# Holoboard_peripherals.net
KiCad netlist of a schematic drawn in Altium Designer
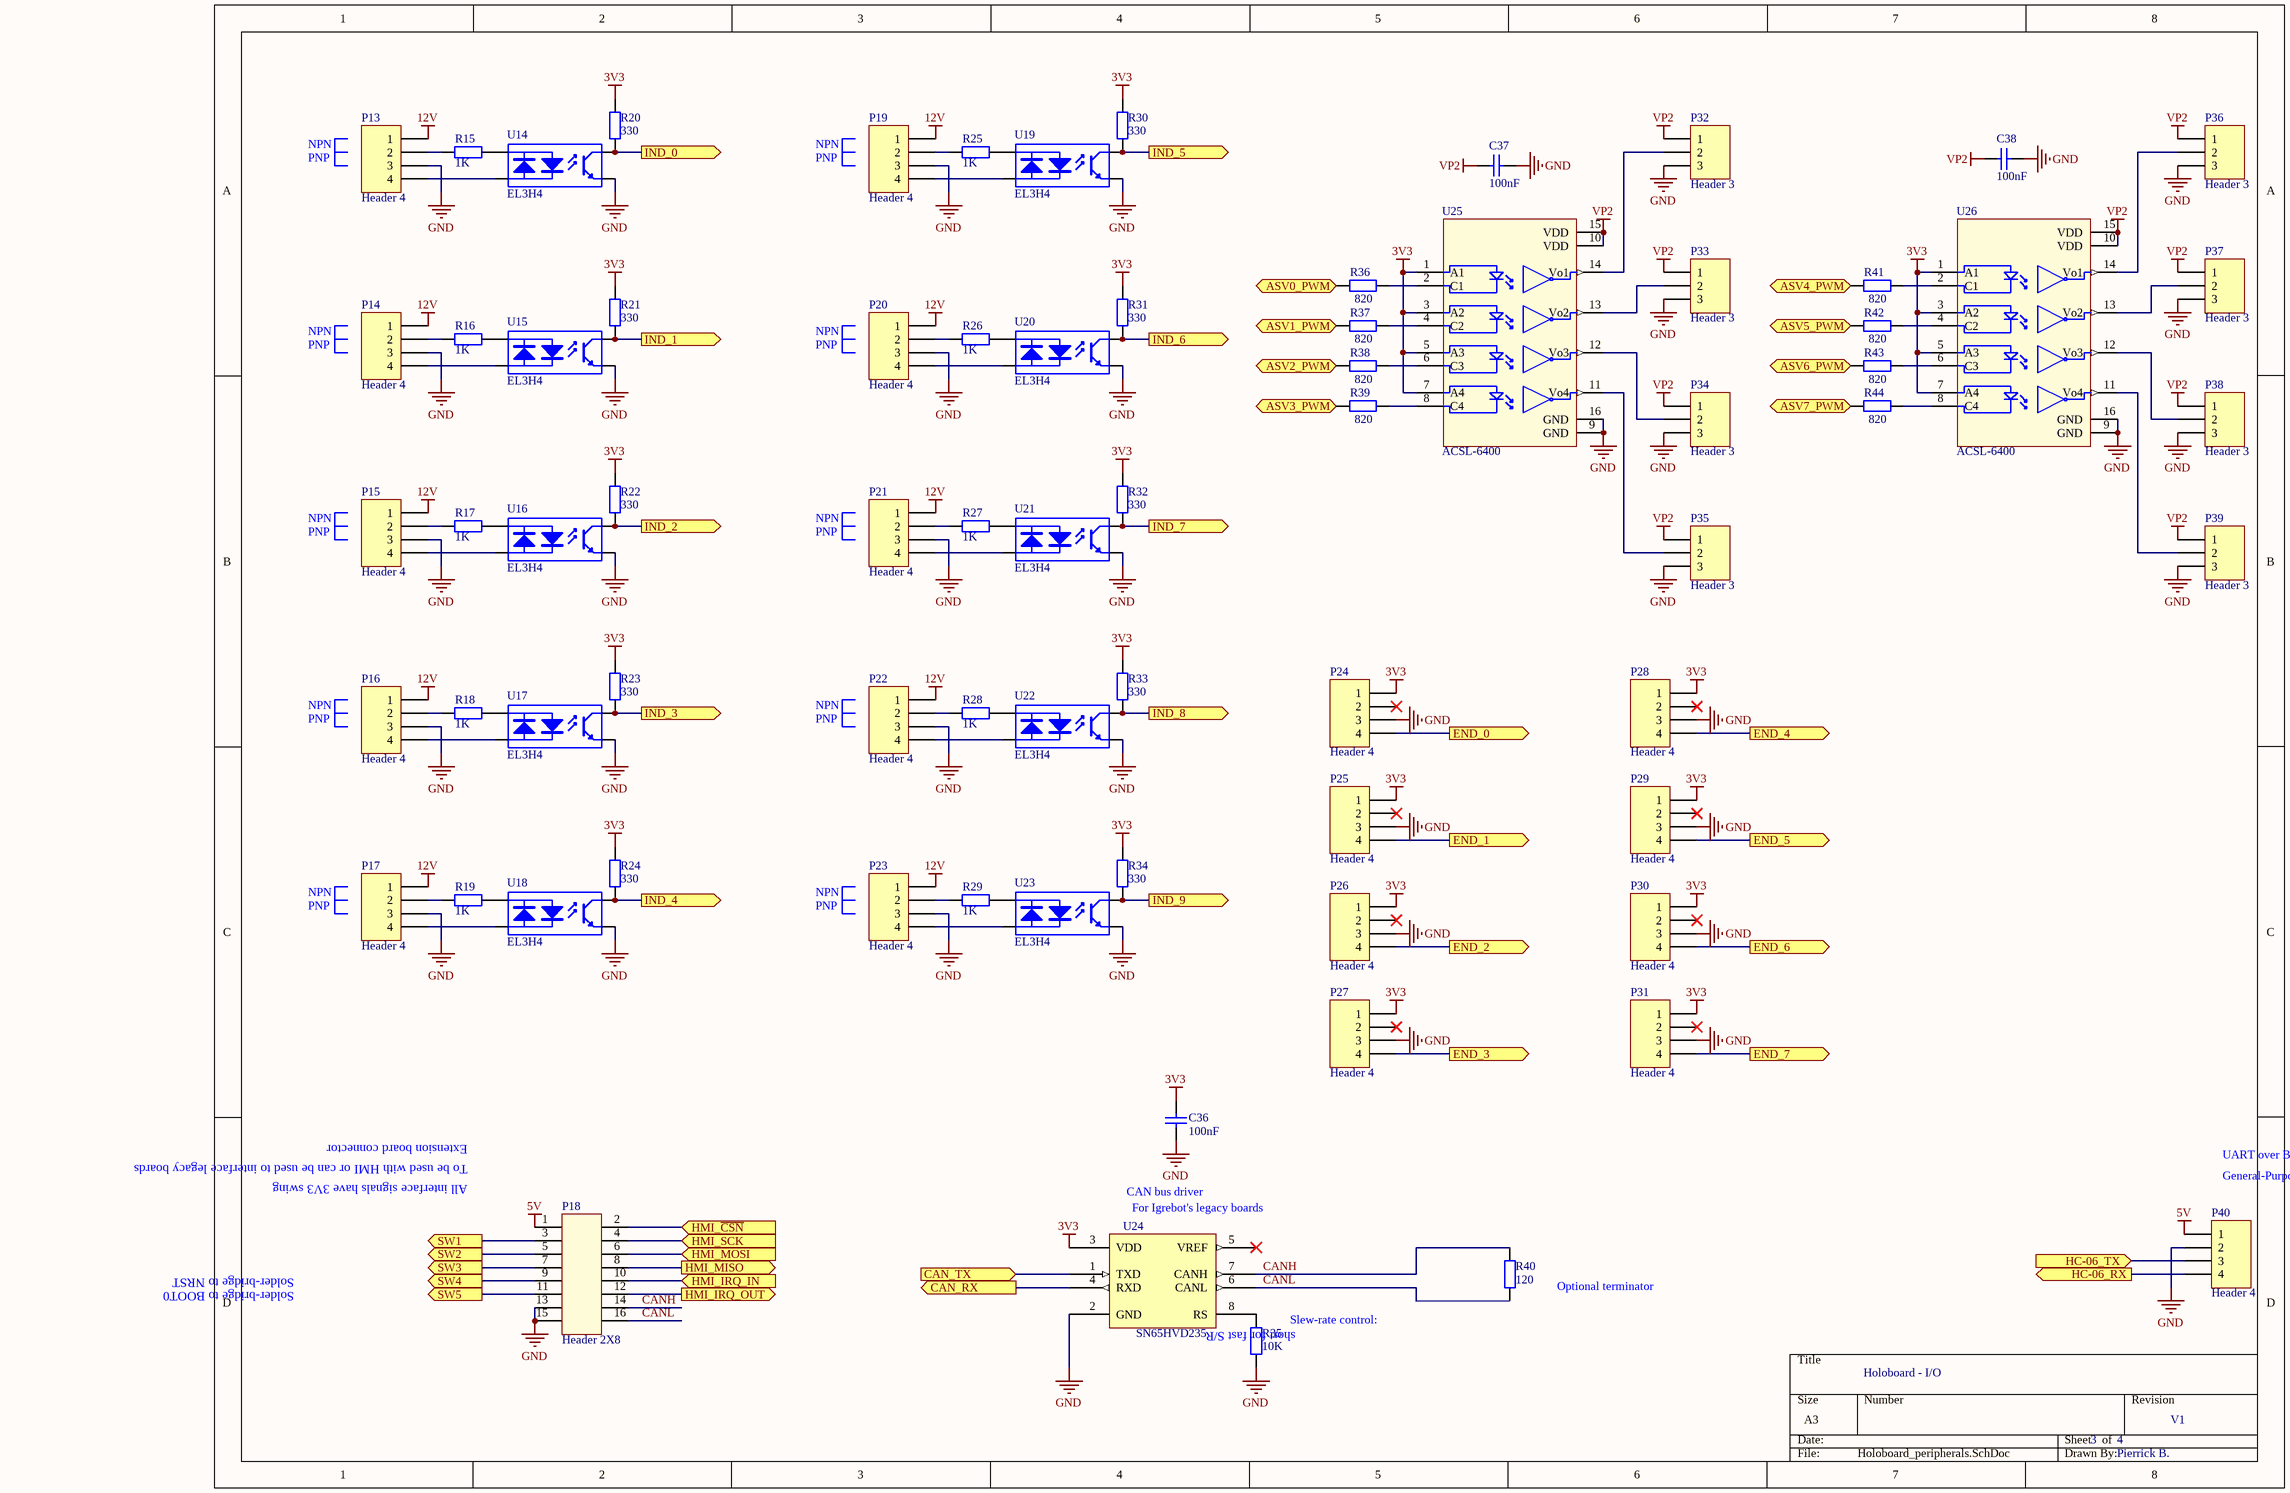
[diagram p0: Holoboard_peripherals.SchDoc]

(export (version "E")
  (design (tool "Eeschema 10.0.6"))
  (components
    (comp (ref "C36")
      (value "100nF")
      (footprint "C0603")
      (description "Capacitor")
      (fields (field (name "Comment") "Cap") (field (name "PUBLISHER") "Altium Limited"))
      (libsource (lib "Miscellaneous Devices") (part "Cap"))
    )
    (comp (ref "C37")
      (value "100nF")
      (footprint "C0603")
      (description "Capacitor")
      (fields (field (name "Comment") "Cap") (field (name "PUBLISHER") "Altium Limited"))
      (libsource (lib "Miscellaneous Devices") (part "Cap"))
    )
    (comp (ref "C38")
      (value "100nF")
      (footprint "C0603")
      (description "Capacitor")
      (fields (field (name "Comment") "Cap") (field (name "PUBLISHER") "Altium Limited"))
      (libsource (lib "Miscellaneous Devices") (part "Cap"))
    )
    (comp (ref "P13")
      (value "Header 4")
      (footprint "7-215079-4")
      (description "Header, 4-Pin")
      (fields (field (name "PUBLISHER") "Altium Limited"))
      (libsource (lib "LIBRARY IGREBOT") (part "Header 4"))
    )
    (comp (ref "P14")
      (value "Header 4")
      (footprint "7-215079-4")
      (description "Header, 4-Pin")
      (fields (field (name "PUBLISHER") "Altium Limited"))
      (libsource (lib "LIBRARY IGREBOT") (part "Header 4"))
    )
    (comp (ref "P15")
      (value "Header 4")
      (footprint "7-215079-4")
      (description "Header, 4-Pin")
      (fields (field (name "PUBLISHER") "Altium Limited"))
      (libsource (lib "LIBRARY IGREBOT") (part "Header 4"))
    )
    (comp (ref "P16")
      (value "Header 4")
      (footprint "7-215079-4")
      (description "Header, 4-Pin")
      (fields (field (name "PUBLISHER") "Altium Limited"))
      (libsource (lib "LIBRARY IGREBOT") (part "Header 4"))
    )
    (comp (ref "P17")
      (value "Header 4")
      (footprint "7-215079-4")
      (description "Header, 4-Pin")
      (fields (field (name "PUBLISHER") "Altium Limited"))
      (libsource (lib "LIBRARY IGREBOT") (part "Header 4"))
    )
    (comp (ref "P18")
      (value "Header 2X8")
      (footprint "HDR2X8")
      (libsource (lib "LIBRARY IGREBOT") (part "Header 2X8"))
    )
    (comp (ref "P19")
      (value "Header 4")
      (footprint "7-215079-4")
      (description "Header, 4-Pin")
      (fields (field (name "PUBLISHER") "Altium Limited"))
      (libsource (lib "LIBRARY IGREBOT") (part "Header 4"))
    )
    (comp (ref "P20")
      (value "Header 4")
      (footprint "7-215079-4")
      (description "Header, 4-Pin")
      (fields (field (name "PUBLISHER") "Altium Limited"))
      (libsource (lib "LIBRARY IGREBOT") (part "Header 4"))
    )
    (comp (ref "P21")
      (value "Header 4")
      (footprint "7-215079-4")
      (description "Header, 4-Pin")
      (fields (field (name "PUBLISHER") "Altium Limited"))
      (libsource (lib "LIBRARY IGREBOT") (part "Header 4"))
    )
    (comp (ref "P22")
      (value "Header 4")
      (footprint "7-215079-4")
      (description "Header, 4-Pin")
      (fields (field (name "PUBLISHER") "Altium Limited"))
      (libsource (lib "LIBRARY IGREBOT") (part "Header 4"))
    )
    (comp (ref "P23")
      (value "Header 4")
      (footprint "7-215079-4")
      (description "Header, 4-Pin")
      (fields (field (name "PUBLISHER") "Altium Limited"))
      (libsource (lib "LIBRARY IGREBOT") (part "Header 4"))
    )
    (comp (ref "P24")
      (value "Header 4")
      (footprint "7-215079-4")
      (description "Header, 4-Pin")
      (fields (field (name "PUBLISHER") "Altium Limited"))
      (libsource (lib "LIBRARY IGREBOT") (part "Header 4"))
    )
    (comp (ref "P25")
      (value "Header 4")
      (footprint "7-215079-4")
      (description "Header, 4-Pin")
      (fields (field (name "PUBLISHER") "Altium Limited"))
      (libsource (lib "LIBRARY IGREBOT") (part "Header 4"))
    )
    (comp (ref "P26")
      (value "Header 4")
      (footprint "7-215079-4")
      (description "Header, 4-Pin")
      (fields (field (name "PUBLISHER") "Altium Limited"))
      (libsource (lib "LIBRARY IGREBOT") (part "Header 4"))
    )
    (comp (ref "P27")
      (value "Header 4")
      (footprint "7-215079-4")
      (description "Header, 4-Pin")
      (fields (field (name "PUBLISHER") "Altium Limited"))
      (libsource (lib "LIBRARY IGREBOT") (part "Header 4"))
    )
    (comp (ref "P28")
      (value "Header 4")
      (footprint "7-215079-4")
      (description "Header, 4-Pin")
      (fields (field (name "PUBLISHER") "Altium Limited"))
      (libsource (lib "LIBRARY IGREBOT") (part "Header 4"))
    )
    (comp (ref "P29")
      (value "Header 4")
      (footprint "7-215079-4")
      (description "Header, 4-Pin")
      (fields (field (name "PUBLISHER") "Altium Limited"))
      (libsource (lib "LIBRARY IGREBOT") (part "Header 4"))
    )
    (comp (ref "P30")
      (value "Header 4")
      (footprint "7-215079-4")
      (description "Header, 4-Pin")
      (fields (field (name "PUBLISHER") "Altium Limited"))
      (libsource (lib "LIBRARY IGREBOT") (part "Header 4"))
    )
    (comp (ref "P31")
      (value "Header 4")
      (footprint "7-215079-4")
      (description "Header, 4-Pin")
      (fields (field (name "PUBLISHER") "Altium Limited"))
      (libsource (lib "LIBRARY IGREBOT") (part "Header 4"))
    )
    (comp (ref "P32")
      (value "Header 3")
      (footprint "HDR1X3")
      (description "Header, 3-Pin")
      (fields (field (name "PUBLISHER") "Altium Limited"))
      (libsource (lib "LIBRARY IGREBOT") (part "Header 3"))
    )
    (comp (ref "P33")
      (value "Header 3")
      (footprint "HDR1X3")
      (description "Header, 3-Pin")
      (fields (field (name "PUBLISHER") "Altium Limited"))
      (libsource (lib "LIBRARY IGREBOT") (part "Header 3"))
    )
    (comp (ref "P34")
      (value "Header 3")
      (footprint "HDR1X3")
      (description "Header, 3-Pin")
      (fields (field (name "PUBLISHER") "Altium Limited"))
      (libsource (lib "LIBRARY IGREBOT") (part "Header 3"))
    )
    (comp (ref "P35")
      (value "Header 3")
      (footprint "HDR1X3")
      (description "Header, 3-Pin")
      (fields (field (name "PUBLISHER") "Altium Limited"))
      (libsource (lib "LIBRARY IGREBOT") (part "Header 3"))
    )
    (comp (ref "P36")
      (value "Header 3")
      (footprint "HDR1X3")
      (description "Header, 3-Pin")
      (fields (field (name "PUBLISHER") "Altium Limited"))
      (libsource (lib "LIBRARY IGREBOT") (part "Header 3"))
    )
    (comp (ref "P37")
      (value "Header 3")
      (footprint "HDR1X3")
      (description "Header, 3-Pin")
      (fields (field (name "PUBLISHER") "Altium Limited"))
      (libsource (lib "LIBRARY IGREBOT") (part "Header 3"))
    )
    (comp (ref "P38")
      (value "Header 3")
      (footprint "HDR1X3")
      (description "Header, 3-Pin")
      (fields (field (name "PUBLISHER") "Altium Limited"))
      (libsource (lib "LIBRARY IGREBOT") (part "Header 3"))
    )
    (comp (ref "P39")
      (value "Header 3")
      (footprint "HDR1X3")
      (description "Header, 3-Pin")
      (fields (field (name "PUBLISHER") "Altium Limited"))
      (libsource (lib "LIBRARY IGREBOT") (part "Header 3"))
    )
    (comp (ref "P40")
      (value "Header 4")
      (footprint "HDR1X4")
      (description "Header, 4-Pin")
      (fields (field (name "PUBLISHER") "Altium Limited"))
      (libsource (lib "") (part "Header 4_1"))
    )
    (comp (ref "R15")
      (value "1K")
      (footprint "0603")
      (description "Resistor")
      (fields (field (name "Comment") "Res2") (field (name "PUBLISHER") "Altium Limited"))
      (libsource (lib "") (part "Res2_1"))
    )
    (comp (ref "R16")
      (value "1K")
      (footprint "0603")
      (description "Resistor")
      (fields (field (name "Comment") "Res2") (field (name "PUBLISHER") "Altium Limited"))
      (libsource (lib "") (part "Res2_1"))
    )
    (comp (ref "R17")
      (value "1K")
      (footprint "0603")
      (description "Resistor")
      (fields (field (name "Comment") "Res2") (field (name "PUBLISHER") "Altium Limited"))
      (libsource (lib "") (part "Res2_1"))
    )
    (comp (ref "R18")
      (value "1K")
      (footprint "0603")
      (description "Resistor")
      (fields (field (name "Comment") "Res2") (field (name "PUBLISHER") "Altium Limited"))
      (libsource (lib "") (part "Res2_1"))
    )
    (comp (ref "R19")
      (value "1K")
      (footprint "0603")
      (description "Resistor")
      (fields (field (name "Comment") "Res2") (field (name "PUBLISHER") "Altium Limited"))
      (libsource (lib "") (part "Res2_1"))
    )
    (comp (ref "R20")
      (value "330")
      (footprint "0603")
      (description "Resistor")
      (fields (field (name "Comment") "Res2") (field (name "PUBLISHER") "Altium Limited"))
      (libsource (lib "LIBRARY IGREBOT") (part "Res2"))
    )
    (comp (ref "R21")
      (value "330")
      (footprint "0603")
      (description "Resistor")
      (fields (field (name "Comment") "Res2") (field (name "PUBLISHER") "Altium Limited"))
      (libsource (lib "LIBRARY IGREBOT") (part "Res2"))
    )
    (comp (ref "R22")
      (value "330")
      (footprint "0603")
      (description "Resistor")
      (fields (field (name "Comment") "Res2") (field (name "PUBLISHER") "Altium Limited"))
      (libsource (lib "LIBRARY IGREBOT") (part "Res2"))
    )
    (comp (ref "R23")
      (value "330")
      (footprint "0603")
      (description "Resistor")
      (fields (field (name "Comment") "Res2") (field (name "PUBLISHER") "Altium Limited"))
      (libsource (lib "LIBRARY IGREBOT") (part "Res2"))
    )
    (comp (ref "R24")
      (value "330")
      (footprint "0603")
      (description "Resistor")
      (fields (field (name "Comment") "Res2") (field (name "PUBLISHER") "Altium Limited"))
      (libsource (lib "LIBRARY IGREBOT") (part "Res2"))
    )
    (comp (ref "R25")
      (value "1K")
      (footprint "0603")
      (description "Resistor")
      (fields (field (name "Comment") "Res2") (field (name "PUBLISHER") "Altium Limited"))
      (libsource (lib "") (part "Res2_1"))
    )
    (comp (ref "R26")
      (value "1K")
      (footprint "0603")
      (description "Resistor")
      (fields (field (name "Comment") "Res2") (field (name "PUBLISHER") "Altium Limited"))
      (libsource (lib "") (part "Res2_1"))
    )
    (comp (ref "R27")
      (value "1K")
      (footprint "0603")
      (description "Resistor")
      (fields (field (name "Comment") "Res2") (field (name "PUBLISHER") "Altium Limited"))
      (libsource (lib "") (part "Res2_1"))
    )
    (comp (ref "R28")
      (value "1K")
      (footprint "0603")
      (description "Resistor")
      (fields (field (name "Comment") "Res2") (field (name "PUBLISHER") "Altium Limited"))
      (libsource (lib "") (part "Res2_1"))
    )
    (comp (ref "R29")
      (value "1K")
      (footprint "0603")
      (description "Resistor")
      (fields (field (name "Comment") "Res2") (field (name "PUBLISHER") "Altium Limited"))
      (libsource (lib "") (part "Res2_1"))
    )
    (comp (ref "R30")
      (value "330")
      (footprint "0603")
      (description "Resistor")
      (fields (field (name "Comment") "Res2") (field (name "PUBLISHER") "Altium Limited"))
      (libsource (lib "LIBRARY IGREBOT") (part "Res2"))
    )
    (comp (ref "R31")
      (value "330")
      (footprint "0603")
      (description "Resistor")
      (fields (field (name "Comment") "Res2") (field (name "PUBLISHER") "Altium Limited"))
      (libsource (lib "LIBRARY IGREBOT") (part "Res2"))
    )
    (comp (ref "R32")
      (value "330")
      (footprint "0603")
      (description "Resistor")
      (fields (field (name "Comment") "Res2") (field (name "PUBLISHER") "Altium Limited"))
      (libsource (lib "LIBRARY IGREBOT") (part "Res2"))
    )
    (comp (ref "R33")
      (value "330")
      (footprint "0603")
      (description "Resistor")
      (fields (field (name "Comment") "Res2") (field (name "PUBLISHER") "Altium Limited"))
      (libsource (lib "LIBRARY IGREBOT") (part "Res2"))
    )
    (comp (ref "R34")
      (value "330")
      (footprint "0603")
      (description "Resistor")
      (fields (field (name "Comment") "Res2") (field (name "PUBLISHER") "Altium Limited"))
      (libsource (lib "LIBRARY IGREBOT") (part "Res2"))
    )
    (comp (ref "R35")
      (value "10K")
      (footprint "0603")
      (description "Resistor")
      (fields (field (name "Comment") "Res2") (field (name "PUBLISHER") "Altium Limited"))
      (libsource (lib "*") (part "Res2"))
    )
    (comp (ref "R36")
      (value "820")
      (footprint "0603")
      (description "Resistor")
      (fields (field (name "Comment") "Res2") (field (name "PUBLISHER") "Altium Limited"))
      (libsource (lib "") (part "Res2_2"))
    )
    (comp (ref "R37")
      (value "820")
      (footprint "0603")
      (description "Resistor")
      (fields (field (name "Comment") "Res2") (field (name "PUBLISHER") "Altium Limited"))
      (libsource (lib "") (part "Res2_2"))
    )
    (comp (ref "R38")
      (value "820")
      (footprint "0603")
      (description "Resistor")
      (fields (field (name "Comment") "Res2") (field (name "PUBLISHER") "Altium Limited"))
      (libsource (lib "") (part "Res2_2"))
    )
    (comp (ref "R39")
      (value "820")
      (footprint "0603")
      (description "Resistor")
      (fields (field (name "Comment") "Res2") (field (name "PUBLISHER") "Altium Limited"))
      (libsource (lib "") (part "Res2_2"))
    )
    (comp (ref "R40")
      (value "120")
      (footprint "0603")
      (description "Resistor")
      (fields (field (name "Comment") "Res2") (field (name "PUBLISHER") "Altium Limited"))
      (libsource (lib "") (part "Res2_1"))
    )
    (comp (ref "R41")
      (value "820")
      (footprint "0603")
      (description "Resistor")
      (fields (field (name "Comment") "Res2") (field (name "PUBLISHER") "Altium Limited"))
      (libsource (lib "") (part "Res2_2"))
    )
    (comp (ref "R42")
      (value "820")
      (footprint "0603")
      (description "Resistor")
      (fields (field (name "Comment") "Res2") (field (name "PUBLISHER") "Altium Limited"))
      (libsource (lib "") (part "Res2_2"))
    )
    (comp (ref "R43")
      (value "820")
      (footprint "0603")
      (description "Resistor")
      (fields (field (name "Comment") "Res2") (field (name "PUBLISHER") "Altium Limited"))
      (libsource (lib "") (part "Res2_2"))
    )
    (comp (ref "R44")
      (value "820")
      (footprint "0603")
      (description "Resistor")
      (fields (field (name "Comment") "Res2") (field (name "PUBLISHER") "Altium Limited"))
      (libsource (lib "") (part "Res2_2"))
    )
    (comp (ref "U14")
      (value "EL3H4")
      (description "4-Pin Phototransistor, AC input")
      (fields (field (name "PUBLISHER") "Altium Limited"))
      (libsource (lib "LIBRARY IGREBOT") (part "EL3H4"))
    )
    (comp (ref "U15")
      (value "EL3H4")
      (description "4-Pin Phototransistor, AC input")
      (fields (field (name "PUBLISHER") "Altium Limited"))
      (libsource (lib "LIBRARY IGREBOT") (part "EL3H4"))
    )
    (comp (ref "U16")
      (value "EL3H4")
      (description "4-Pin Phototransistor, AC input")
      (fields (field (name "PUBLISHER") "Altium Limited"))
      (libsource (lib "LIBRARY IGREBOT") (part "EL3H4"))
    )
    (comp (ref "U17")
      (value "EL3H4")
      (description "4-Pin Phototransistor, AC input")
      (fields (field (name "PUBLISHER") "Altium Limited"))
      (libsource (lib "LIBRARY IGREBOT") (part "EL3H4"))
    )
    (comp (ref "U18")
      (value "EL3H4")
      (description "4-Pin Phototransistor, AC input")
      (fields (field (name "PUBLISHER") "Altium Limited"))
      (libsource (lib "LIBRARY IGREBOT") (part "EL3H4"))
    )
    (comp (ref "U19")
      (value "EL3H4")
      (description "4-Pin Phototransistor, AC input")
      (fields (field (name "PUBLISHER") "Altium Limited"))
      (libsource (lib "LIBRARY IGREBOT") (part "EL3H4"))
    )
    (comp (ref "U20")
      (value "EL3H4")
      (description "4-Pin Phototransistor, AC input")
      (fields (field (name "PUBLISHER") "Altium Limited"))
      (libsource (lib "LIBRARY IGREBOT") (part "EL3H4"))
    )
    (comp (ref "U21")
      (value "EL3H4")
      (description "4-Pin Phototransistor, AC input")
      (fields (field (name "PUBLISHER") "Altium Limited"))
      (libsource (lib "LIBRARY IGREBOT") (part "EL3H4"))
    )
    (comp (ref "U22")
      (value "EL3H4")
      (description "4-Pin Phototransistor, AC input")
      (fields (field (name "PUBLISHER") "Altium Limited"))
      (libsource (lib "LIBRARY IGREBOT") (part "EL3H4"))
    )
    (comp (ref "U23")
      (value "EL3H4")
      (description "4-Pin Phototransistor, AC input")
      (fields (field (name "PUBLISHER") "Altium Limited"))
      (libsource (lib "LIBRARY IGREBOT") (part "EL3H4"))
    )
    (comp (ref "U24")
      (value "SN65HVD235")
      (footprint "SOIC150-8")
      (description "High Speed Can Transceiver")
      (fields (field (name "PUBLISHER") "Altium Limited"))
      (libsource (lib "*") (part "MCP2551"))
    )
    (comp (ref "U25")
      (value "ACSL-6400")
      (footprint "SO16")
      (libsource (lib "LIBRARY IGREBOT") (part "ACSL-6400"))
    )
    (comp (ref "U26")
      (value "ACSL-6400")
      (footprint "SO16")
      (libsource (lib "LIBRARY IGREBOT") (part "ACSL-6400"))
    )
  )
  (nets
    (net (code "1") (name "/ASV0_PWM") (class "Default")
      (node (ref "R36") (pin "1") (pinfunction "1_1") (pintype "passive"))
    )
    (net (code "2") (name "/ASV1_PWM") (class "Default")
      (node (ref "R37") (pin "1") (pinfunction "1_1") (pintype "passive"))
    )
    (net (code "3") (name "/ASV2_PWM") (class "Default")
      (node (ref "R38") (pin "1") (pinfunction "1_1") (pintype "passive"))
    )
    (net (code "4") (name "/ASV3_PWM") (class "Default")
      (node (ref "R39") (pin "1") (pinfunction "1_1") (pintype "passive"))
    )
    (net (code "5") (name "/ASV4_PWM") (class "Default")
      (node (ref "R41") (pin "1") (pinfunction "1_1") (pintype "passive"))
    )
    (net (code "6") (name "/ASV5_PWM") (class "Default")
      (node (ref "R42") (pin "1") (pinfunction "1_1") (pintype "passive"))
    )
    (net (code "7") (name "/ASV6_PWM") (class "Default")
      (node (ref "R43") (pin "1") (pinfunction "1_1") (pintype "passive"))
    )
    (net (code "8") (name "/ASV7_PWM") (class "Default")
      (node (ref "R44") (pin "1") (pinfunction "1_1") (pintype "passive"))
    )
    (net (code "9") (name "/CANH") (class "Default")
      (node (ref "P18") (pin "14") (pinfunction "14_14") (pintype "passive"))
      (node (ref "R40") (pin "1") (pinfunction "1_1") (pintype "passive"))
      (node (ref "U24") (pin "7") (pinfunction "CANH_7") (pintype "output"))
    )
    (net (code "10") (name "/CANL") (class "Default")
      (node (ref "P18") (pin "16") (pinfunction "16_16") (pintype "passive"))
      (node (ref "R40") (pin "2") (pinfunction "2_2") (pintype "passive"))
      (node (ref "U24") (pin "6") (pinfunction "CANL_6") (pintype "output"))
    )
    (net (code "11") (name "/CAN_RX") (class "Default")
      (node (ref "U24") (pin "4") (pinfunction "RXD_4") (pintype "output"))
    )
    (net (code "12") (name "/CAN_TX") (class "Default")
      (node (ref "U24") (pin "1") (pinfunction "TXD_1") (pintype "input"))
    )
    (net (code "13") (name "/END_0") (class "Default")
      (node (ref "P24") (pin "4") (pinfunction "4_4") (pintype "passive"))
    )
    (net (code "14") (name "/END_1") (class "Default")
      (node (ref "P25") (pin "4") (pinfunction "4_4") (pintype "passive"))
    )
    (net (code "15") (name "/END_2") (class "Default")
      (node (ref "P26") (pin "4") (pinfunction "4_4") (pintype "passive"))
    )
    (net (code "16") (name "/END_3") (class "Default")
      (node (ref "P27") (pin "4") (pinfunction "4_4") (pintype "passive"))
    )
    (net (code "17") (name "/END_4") (class "Default")
      (node (ref "P28") (pin "4") (pinfunction "4_4") (pintype "passive"))
    )
    (net (code "18") (name "/END_5") (class "Default")
      (node (ref "P29") (pin "4") (pinfunction "4_4") (pintype "passive"))
    )
    (net (code "19") (name "/END_6") (class "Default")
      (node (ref "P30") (pin "4") (pinfunction "4_4") (pintype "passive"))
    )
    (net (code "20") (name "/END_7") (class "Default")
      (node (ref "P31") (pin "4") (pinfunction "4_4") (pintype "passive"))
    )
    (net (code "21") (name "/HC-06_RX") (class "Default")
      (node (ref "P40") (pin "4") (pinfunction "4_4") (pintype "passive"))
    )
    (net (code "22") (name "/HC-06_TX") (class "Default")
      (node (ref "P40") (pin "3") (pinfunction "3_3") (pintype "passive"))
    )
    (net (code "23") (name "/HMI_IRQ_IN") (class "Default")
      (node (ref "P18") (pin "10") (pinfunction "10_10") (pintype "passive"))
    )
    (net (code "24") (name "/HMI_IRQ_OUT") (class "Default")
      (node (ref "P18") (pin "12") (pinfunction "12_12") (pintype "passive"))
    )
    (net (code "25") (name "/HMI_MISO") (class "Default")
      (node (ref "P18") (pin "8") (pinfunction "8_8") (pintype "passive"))
    )
    (net (code "26") (name "/HMI_MOSI") (class "Default")
      (node (ref "P18") (pin "6") (pinfunction "6_6") (pintype "passive"))
    )
    (net (code "27") (name "/HMI_SCK") (class "Default")
      (node (ref "P18") (pin "4") (pinfunction "4_4") (pintype "passive"))
    )
    (net (code "28") (name "/HMI_~{CSN}") (class "Default")
      (node (ref "P18") (pin "2") (pinfunction "2_2") (pintype "passive"))
    )
    (net (code "29") (name "/IND_0") (class "Default")
      (node (ref "R20") (pin "2") (pinfunction "2_2") (pintype "passive"))
      (node (ref "U14") (pin "4") (pinfunction "C_4") (pintype "passive"))
    )
    (net (code "30") (name "/IND_1") (class "Default")
      (node (ref "R21") (pin "2") (pinfunction "2_2") (pintype "passive"))
      (node (ref "U15") (pin "4") (pinfunction "C_4") (pintype "passive"))
    )
    (net (code "31") (name "/IND_2") (class "Default")
      (node (ref "R22") (pin "2") (pinfunction "2_2") (pintype "passive"))
      (node (ref "U16") (pin "4") (pinfunction "C_4") (pintype "passive"))
    )
    (net (code "32") (name "/IND_3") (class "Default")
      (node (ref "R23") (pin "2") (pinfunction "2_2") (pintype "passive"))
      (node (ref "U17") (pin "4") (pinfunction "C_4") (pintype "passive"))
    )
    (net (code "33") (name "/IND_4") (class "Default")
      (node (ref "R24") (pin "2") (pinfunction "2_2") (pintype "passive"))
      (node (ref "U18") (pin "4") (pinfunction "C_4") (pintype "passive"))
    )
    (net (code "34") (name "/IND_5") (class "Default")
      (node (ref "R30") (pin "2") (pinfunction "2_2") (pintype "passive"))
      (node (ref "U19") (pin "4") (pinfunction "C_4") (pintype "passive"))
    )
    (net (code "35") (name "/IND_6") (class "Default")
      (node (ref "R31") (pin "2") (pinfunction "2_2") (pintype "passive"))
      (node (ref "U20") (pin "4") (pinfunction "C_4") (pintype "passive"))
    )
    (net (code "36") (name "/IND_7") (class "Default")
      (node (ref "R32") (pin "2") (pinfunction "2_2") (pintype "passive"))
      (node (ref "U21") (pin "4") (pinfunction "C_4") (pintype "passive"))
    )
    (net (code "37") (name "/IND_8") (class "Default")
      (node (ref "R33") (pin "2") (pinfunction "2_2") (pintype "passive"))
      (node (ref "U22") (pin "4") (pinfunction "C_4") (pintype "passive"))
    )
    (net (code "38") (name "/IND_9") (class "Default")
      (node (ref "R34") (pin "2") (pinfunction "2_2") (pintype "passive"))
      (node (ref "U23") (pin "4") (pinfunction "C_4") (pintype "passive"))
    )
    (net (code "39") (name "/SW1") (class "Default")
      (node (ref "P18") (pin "3") (pinfunction "3_3") (pintype "passive"))
    )
    (net (code "40") (name "/SW2") (class "Default")
      (node (ref "P18") (pin "5") (pinfunction "5_5") (pintype "passive"))
    )
    (net (code "41") (name "/SW3") (class "Default")
      (node (ref "P18") (pin "7") (pinfunction "7_7") (pintype "passive"))
    )
    (net (code "42") (name "/SW4") (class "Default")
      (node (ref "P18") (pin "9") (pinfunction "9_9") (pintype "passive"))
    )
    (net (code "43") (name "/SW5") (class "Default")
      (node (ref "P18") (pin "11") (pinfunction "11_11") (pintype "passive"))
    )
    (net (code "44") (name "3V3") (class "Default")
      (node (ref "C36") (pin "2") (pinfunction "2_2") (pintype "passive"))
      (node (ref "P24") (pin "1") (pinfunction "1_1") (pintype "passive"))
      (node (ref "P25") (pin "1") (pinfunction "1_1") (pintype "passive"))
      (node (ref "P26") (pin "1") (pinfunction "1_1") (pintype "passive"))
      (node (ref "P27") (pin "1") (pinfunction "1_1") (pintype "passive"))
      (node (ref "P28") (pin "1") (pinfunction "1_1") (pintype "passive"))
      (node (ref "P29") (pin "1") (pinfunction "1_1") (pintype "passive"))
      (node (ref "P30") (pin "1") (pinfunction "1_1") (pintype "passive"))
      (node (ref "P31") (pin "1") (pinfunction "1_1") (pintype "passive"))
      (node (ref "R20") (pin "1") (pinfunction "1_1") (pintype "passive"))
      (node (ref "R21") (pin "1") (pinfunction "1_1") (pintype "passive"))
      (node (ref "R22") (pin "1") (pinfunction "1_1") (pintype "passive"))
      (node (ref "R23") (pin "1") (pinfunction "1_1") (pintype "passive"))
      (node (ref "R24") (pin "1") (pinfunction "1_1") (pintype "passive"))
      (node (ref "R30") (pin "1") (pinfunction "1_1") (pintype "passive"))
      (node (ref "R31") (pin "1") (pinfunction "1_1") (pintype "passive"))
      (node (ref "R32") (pin "1") (pinfunction "1_1") (pintype "passive"))
      (node (ref "R33") (pin "1") (pinfunction "1_1") (pintype "passive"))
      (node (ref "R34") (pin "1") (pinfunction "1_1") (pintype "passive"))
      (node (ref "U24") (pin "3") (pinfunction "VDD_3") (pintype "power_in"))
      (node (ref "U25") (pin "1") (pinfunction "A1_1") (pintype "power_in"))
      (node (ref "U25") (pin "3") (pinfunction "A2_3") (pintype "passive"))
      (node (ref "U25") (pin "5") (pinfunction "A3_5") (pintype "passive"))
      (node (ref "U25") (pin "7") (pinfunction "A4_7") (pintype "passive"))
      (node (ref "U26") (pin "1") (pinfunction "A1_1") (pintype "power_in"))
      (node (ref "U26") (pin "3") (pinfunction "A2_3") (pintype "passive"))
      (node (ref "U26") (pin "5") (pinfunction "A3_5") (pintype "passive"))
      (node (ref "U26") (pin "7") (pinfunction "A4_7") (pintype "passive"))
    )
    (net (code "45") (name "5V") (class "Default")
      (node (ref "P18") (pin "1") (pinfunction "1_1") (pintype "passive"))
      (node (ref "P40") (pin "1") (pinfunction "1_1") (pintype "passive"))
    )
    (net (code "46") (name "12V") (class "Default")
      (node (ref "P13") (pin "1") (pinfunction "1_1") (pintype "passive"))
      (node (ref "P14") (pin "1") (pinfunction "1_1") (pintype "passive"))
      (node (ref "P15") (pin "1") (pinfunction "1_1") (pintype "passive"))
      (node (ref "P16") (pin "1") (pinfunction "1_1") (pintype "passive"))
      (node (ref "P17") (pin "1") (pinfunction "1_1") (pintype "passive"))
      (node (ref "P19") (pin "1") (pinfunction "1_1") (pintype "passive"))
      (node (ref "P20") (pin "1") (pinfunction "1_1") (pintype "passive"))
      (node (ref "P21") (pin "1") (pinfunction "1_1") (pintype "passive"))
      (node (ref "P22") (pin "1") (pinfunction "1_1") (pintype "passive"))
      (node (ref "P23") (pin "1") (pinfunction "1_1") (pintype "passive"))
    )
    (net (code "47") (name "GND") (class "Default")
      (node (ref "C36") (pin "1") (pinfunction "1_1") (pintype "passive"))
      (node (ref "C37") (pin "1") (pinfunction "1_1") (pintype "passive"))
      (node (ref "C38") (pin "1") (pinfunction "1_1") (pintype "passive"))
      (node (ref "P13") (pin "3") (pinfunction "3_3") (pintype "passive"))
      (node (ref "P14") (pin "3") (pinfunction "3_3") (pintype "passive"))
      (node (ref "P15") (pin "3") (pinfunction "3_3") (pintype "passive"))
      (node (ref "P16") (pin "3") (pinfunction "3_3") (pintype "passive"))
      (node (ref "P17") (pin "3") (pinfunction "3_3") (pintype "passive"))
      (node (ref "P18") (pin "13") (pinfunction "13_13") (pintype "passive"))
      (node (ref "P18") (pin "15") (pinfunction "15_15") (pintype "passive"))
      (node (ref "P19") (pin "3") (pinfunction "3_3") (pintype "passive"))
      (node (ref "P20") (pin "3") (pinfunction "3_3") (pintype "passive"))
      (node (ref "P21") (pin "3") (pinfunction "3_3") (pintype "passive"))
      (node (ref "P22") (pin "3") (pinfunction "3_3") (pintype "passive"))
      (node (ref "P23") (pin "3") (pinfunction "3_3") (pintype "passive"))
      (node (ref "P24") (pin "3") (pinfunction "3_3") (pintype "passive"))
      (node (ref "P25") (pin "3") (pinfunction "3_3") (pintype "passive"))
      (node (ref "P26") (pin "3") (pinfunction "3_3") (pintype "passive"))
      (node (ref "P27") (pin "3") (pinfunction "3_3") (pintype "passive"))
      (node (ref "P28") (pin "3") (pinfunction "3_3") (pintype "passive"))
      (node (ref "P29") (pin "3") (pinfunction "3_3") (pintype "passive"))
      (node (ref "P30") (pin "3") (pinfunction "3_3") (pintype "passive"))
      (node (ref "P31") (pin "3") (pinfunction "3_3") (pintype "passive"))
      (node (ref "P32") (pin "3") (pinfunction "3_3") (pintype "passive"))
      (node (ref "P33") (pin "3") (pinfunction "3_3") (pintype "passive"))
      (node (ref "P34") (pin "3") (pinfunction "3_3") (pintype "passive"))
      (node (ref "P35") (pin "3") (pinfunction "3_3") (pintype "passive"))
      (node (ref "P36") (pin "3") (pinfunction "3_3") (pintype "passive"))
      (node (ref "P37") (pin "3") (pinfunction "3_3") (pintype "passive"))
      (node (ref "P38") (pin "3") (pinfunction "3_3") (pintype "passive"))
      (node (ref "P39") (pin "3") (pinfunction "3_3") (pintype "passive"))
      (node (ref "P40") (pin "2") (pinfunction "2_2") (pintype "passive"))
      (node (ref "R35") (pin "1") (pinfunction "1_1") (pintype "passive"))
      (node (ref "U14") (pin "3") (pinfunction "E_3") (pintype "passive"))
      (node (ref "U15") (pin "3") (pinfunction "E_3") (pintype "passive"))
      (node (ref "U16") (pin "3") (pinfunction "E_3") (pintype "passive"))
      (node (ref "U17") (pin "3") (pinfunction "E_3") (pintype "passive"))
      (node (ref "U18") (pin "3") (pinfunction "E_3") (pintype "passive"))
      (node (ref "U19") (pin "3") (pinfunction "E_3") (pintype "passive"))
      (node (ref "U20") (pin "3") (pinfunction "E_3") (pintype "passive"))
      (node (ref "U21") (pin "3") (pinfunction "E_3") (pintype "passive"))
      (node (ref "U22") (pin "3") (pinfunction "E_3") (pintype "passive"))
      (node (ref "U23") (pin "3") (pinfunction "E_3") (pintype "passive"))
      (node (ref "U24") (pin "2") (pinfunction "GND_2") (pintype "power_in"))
      (node (ref "U25") (pin "16") (pinfunction "GND_16") (pintype "power_in"))
      (node (ref "U25") (pin "9") (pinfunction "GND_9") (pintype "power_in"))
      (node (ref "U26") (pin "16") (pinfunction "GND_16") (pintype "power_in"))
      (node (ref "U26") (pin "9") (pinfunction "GND_9") (pintype "power_in"))
    )
    (net (code "48") (name "Net-(P13-Pad2)") (class "Default")
      (node (ref "P13") (pin "2") (pinfunction "2_2") (pintype "passive"))
      (node (ref "R15") (pin "2") (pinfunction "2_2") (pintype "passive"))
    )
    (net (code "49") (name "Net-(P14-Pad2)") (class "Default")
      (node (ref "P14") (pin "2") (pinfunction "2_2") (pintype "passive"))
      (node (ref "R16") (pin "2") (pinfunction "2_2") (pintype "passive"))
    )
    (net (code "50") (name "Net-(P15-Pad2)") (class "Default")
      (node (ref "P15") (pin "2") (pinfunction "2_2") (pintype "passive"))
      (node (ref "R17") (pin "2") (pinfunction "2_2") (pintype "passive"))
    )
    (net (code "51") (name "Net-(P16-Pad2)") (class "Default")
      (node (ref "P16") (pin "2") (pinfunction "2_2") (pintype "passive"))
      (node (ref "R18") (pin "2") (pinfunction "2_2") (pintype "passive"))
    )
    (net (code "52") (name "Net-(P17-Pad2)") (class "Default")
      (node (ref "P17") (pin "2") (pinfunction "2_2") (pintype "passive"))
      (node (ref "R19") (pin "2") (pinfunction "2_2") (pintype "passive"))
    )
    (net (code "53") (name "Net-(P19-Pad2)") (class "Default")
      (node (ref "P19") (pin "2") (pinfunction "2_2") (pintype "passive"))
      (node (ref "R25") (pin "2") (pinfunction "2_2") (pintype "passive"))
    )
    (net (code "54") (name "Net-(P20-Pad2)") (class "Default")
      (node (ref "P20") (pin "2") (pinfunction "2_2") (pintype "passive"))
      (node (ref "R26") (pin "2") (pinfunction "2_2") (pintype "passive"))
    )
    (net (code "55") (name "Net-(P21-Pad2)") (class "Default")
      (node (ref "P21") (pin "2") (pinfunction "2_2") (pintype "passive"))
      (node (ref "R27") (pin "2") (pinfunction "2_2") (pintype "passive"))
    )
    (net (code "56") (name "Net-(P22-Pad2)") (class "Default")
      (node (ref "P22") (pin "2") (pinfunction "2_2") (pintype "passive"))
      (node (ref "R28") (pin "2") (pinfunction "2_2") (pintype "passive"))
    )
    (net (code "57") (name "Net-(P23-Pad2)") (class "Default")
      (node (ref "P23") (pin "2") (pinfunction "2_2") (pintype "passive"))
      (node (ref "R29") (pin "2") (pinfunction "2_2") (pintype "passive"))
    )
    (net (code "58") (name "Net-(U14-A)") (class "Default")
      (node (ref "R15") (pin "1") (pinfunction "1_1") (pintype "passive"))
      (node (ref "U14") (pin "1") (pinfunction "A_1") (pintype "passive"))
    )
    (net (code "59") (name "Net-(U14-K)") (class "Default")
      (node (ref "P13") (pin "4") (pinfunction "4_4") (pintype "passive"))
      (node (ref "U14") (pin "2") (pinfunction "K_2") (pintype "passive"))
    )
    (net (code "60") (name "Net-(U15-A)") (class "Default")
      (node (ref "R16") (pin "1") (pinfunction "1_1") (pintype "passive"))
      (node (ref "U15") (pin "1") (pinfunction "A_1") (pintype "passive"))
    )
    (net (code "61") (name "Net-(U15-K)") (class "Default")
      (node (ref "P14") (pin "4") (pinfunction "4_4") (pintype "passive"))
      (node (ref "U15") (pin "2") (pinfunction "K_2") (pintype "passive"))
    )
    (net (code "62") (name "Net-(U16-A)") (class "Default")
      (node (ref "R17") (pin "1") (pinfunction "1_1") (pintype "passive"))
      (node (ref "U16") (pin "1") (pinfunction "A_1") (pintype "passive"))
    )
    (net (code "63") (name "Net-(U16-K)") (class "Default")
      (node (ref "P15") (pin "4") (pinfunction "4_4") (pintype "passive"))
      (node (ref "U16") (pin "2") (pinfunction "K_2") (pintype "passive"))
    )
    (net (code "64") (name "Net-(U17-A)") (class "Default")
      (node (ref "R18") (pin "1") (pinfunction "1_1") (pintype "passive"))
      (node (ref "U17") (pin "1") (pinfunction "A_1") (pintype "passive"))
    )
    (net (code "65") (name "Net-(U17-K)") (class "Default")
      (node (ref "P16") (pin "4") (pinfunction "4_4") (pintype "passive"))
      (node (ref "U17") (pin "2") (pinfunction "K_2") (pintype "passive"))
    )
    (net (code "66") (name "Net-(U18-A)") (class "Default")
      (node (ref "R19") (pin "1") (pinfunction "1_1") (pintype "passive"))
      (node (ref "U18") (pin "1") (pinfunction "A_1") (pintype "passive"))
    )
    (net (code "67") (name "Net-(U18-K)") (class "Default")
      (node (ref "P17") (pin "4") (pinfunction "4_4") (pintype "passive"))
      (node (ref "U18") (pin "2") (pinfunction "K_2") (pintype "passive"))
    )
    (net (code "68") (name "Net-(U19-A)") (class "Default")
      (node (ref "R25") (pin "1") (pinfunction "1_1") (pintype "passive"))
      (node (ref "U19") (pin "1") (pinfunction "A_1") (pintype "passive"))
    )
    (net (code "69") (name "Net-(U19-K)") (class "Default")
      (node (ref "P19") (pin "4") (pinfunction "4_4") (pintype "passive"))
      (node (ref "U19") (pin "2") (pinfunction "K_2") (pintype "passive"))
    )
    (net (code "70") (name "Net-(U20-A)") (class "Default")
      (node (ref "R26") (pin "1") (pinfunction "1_1") (pintype "passive"))
      (node (ref "U20") (pin "1") (pinfunction "A_1") (pintype "passive"))
    )
    (net (code "71") (name "Net-(U20-K)") (class "Default")
      (node (ref "P20") (pin "4") (pinfunction "4_4") (pintype "passive"))
      (node (ref "U20") (pin "2") (pinfunction "K_2") (pintype "passive"))
    )
    (net (code "72") (name "Net-(U21-A)") (class "Default")
      (node (ref "R27") (pin "1") (pinfunction "1_1") (pintype "passive"))
      (node (ref "U21") (pin "1") (pinfunction "A_1") (pintype "passive"))
    )
    (net (code "73") (name "Net-(U21-K)") (class "Default")
      (node (ref "P21") (pin "4") (pinfunction "4_4") (pintype "passive"))
      (node (ref "U21") (pin "2") (pinfunction "K_2") (pintype "passive"))
    )
    (net (code "74") (name "Net-(U22-A)") (class "Default")
      (node (ref "R28") (pin "1") (pinfunction "1_1") (pintype "passive"))
      (node (ref "U22") (pin "1") (pinfunction "A_1") (pintype "passive"))
    )
    (net (code "75") (name "Net-(U22-K)") (class "Default")
      (node (ref "P22") (pin "4") (pinfunction "4_4") (pintype "passive"))
      (node (ref "U22") (pin "2") (pinfunction "K_2") (pintype "passive"))
    )
    (net (code "76") (name "Net-(U23-A)") (class "Default")
      (node (ref "R29") (pin "1") (pinfunction "1_1") (pintype "passive"))
      (node (ref "U23") (pin "1") (pinfunction "A_1") (pintype "passive"))
    )
    (net (code "77") (name "Net-(U23-K)") (class "Default")
      (node (ref "P23") (pin "4") (pinfunction "4_4") (pintype "passive"))
      (node (ref "U23") (pin "2") (pinfunction "K_2") (pintype "passive"))
    )
    (net (code "78") (name "Net-(U24-RS)") (class "Default")
      (node (ref "R35") (pin "2") (pinfunction "2_2") (pintype "passive"))
      (node (ref "U24") (pin "8") (pinfunction "RS_8") (pintype "passive"))
    )
    (net (code "79") (name "Net-(U25-C1)") (class "Default")
      (node (ref "R36") (pin "2") (pinfunction "2_2") (pintype "passive"))
      (node (ref "U25") (pin "2") (pinfunction "C1_2") (pintype "passive"))
    )
    (net (code "80") (name "Net-(U25-C2)") (class "Default")
      (node (ref "R37") (pin "2") (pinfunction "2_2") (pintype "passive"))
      (node (ref "U25") (pin "4") (pinfunction "C2_4") (pintype "passive"))
    )
    (net (code "81") (name "Net-(U25-C3)") (class "Default")
      (node (ref "R38") (pin "2") (pinfunction "2_2") (pintype "passive"))
      (node (ref "U25") (pin "6") (pinfunction "C3_6") (pintype "passive"))
    )
    (net (code "82") (name "Net-(U25-C4)") (class "Default")
      (node (ref "R39") (pin "2") (pinfunction "2_2") (pintype "passive"))
      (node (ref "U25") (pin "8") (pinfunction "C4_8") (pintype "passive"))
    )
    (net (code "83") (name "Net-(U25-Vo1)") (class "Default")
      (node (ref "P32") (pin "2") (pinfunction "2_2") (pintype "passive"))
      (node (ref "U25") (pin "14") (pinfunction "Vo1_14") (pintype "output"))
    )
    (net (code "84") (name "Net-(U25-Vo2)") (class "Default")
      (node (ref "P33") (pin "2") (pinfunction "2_2") (pintype "passive"))
      (node (ref "U25") (pin "13") (pinfunction "Vo2_13") (pintype "output"))
    )
    (net (code "85") (name "Net-(U25-Vo3)") (class "Default")
      (node (ref "P34") (pin "2") (pinfunction "2_2") (pintype "passive"))
      (node (ref "U25") (pin "12") (pinfunction "Vo3_12") (pintype "output"))
    )
    (net (code "86") (name "Net-(U25-Vo4)") (class "Default")
      (node (ref "P35") (pin "2") (pinfunction "2_2") (pintype "passive"))
      (node (ref "U25") (pin "11") (pinfunction "Vo4_11") (pintype "output"))
    )
    (net (code "87") (name "Net-(U26-C1)") (class "Default")
      (node (ref "R41") (pin "2") (pinfunction "2_2") (pintype "passive"))
      (node (ref "U26") (pin "2") (pinfunction "C1_2") (pintype "passive"))
    )
    (net (code "88") (name "Net-(U26-C2)") (class "Default")
      (node (ref "R42") (pin "2") (pinfunction "2_2") (pintype "passive"))
      (node (ref "U26") (pin "4") (pinfunction "C2_4") (pintype "passive"))
    )
    (net (code "89") (name "Net-(U26-C3)") (class "Default")
      (node (ref "R43") (pin "2") (pinfunction "2_2") (pintype "passive"))
      (node (ref "U26") (pin "6") (pinfunction "C3_6") (pintype "passive"))
    )
    (net (code "90") (name "Net-(U26-C4)") (class "Default")
      (node (ref "R44") (pin "2") (pinfunction "2_2") (pintype "passive"))
      (node (ref "U26") (pin "8") (pinfunction "C4_8") (pintype "passive"))
    )
    (net (code "91") (name "Net-(U26-Vo1)") (class "Default")
      (node (ref "P36") (pin "2") (pinfunction "2_2") (pintype "passive"))
      (node (ref "U26") (pin "14") (pinfunction "Vo1_14") (pintype "output"))
    )
    (net (code "92") (name "Net-(U26-Vo2)") (class "Default")
      (node (ref "P37") (pin "2") (pinfunction "2_2") (pintype "passive"))
      (node (ref "U26") (pin "13") (pinfunction "Vo2_13") (pintype "output"))
    )
    (net (code "93") (name "Net-(U26-Vo3)") (class "Default")
      (node (ref "P38") (pin "2") (pinfunction "2_2") (pintype "passive"))
      (node (ref "U26") (pin "12") (pinfunction "Vo3_12") (pintype "output"))
    )
    (net (code "94") (name "Net-(U26-Vo4)") (class "Default")
      (node (ref "P39") (pin "2") (pinfunction "2_2") (pintype "passive"))
      (node (ref "U26") (pin "11") (pinfunction "Vo4_11") (pintype "output"))
    )
    (net (code "95") (name "VP2") (class "Default")
      (node (ref "C37") (pin "2") (pinfunction "2_2") (pintype "passive"))
      (node (ref "C38") (pin "2") (pinfunction "2_2") (pintype "passive"))
      (node (ref "P32") (pin "1") (pinfunction "1_1") (pintype "passive"))
      (node (ref "P33") (pin "1") (pinfunction "1_1") (pintype "passive"))
      (node (ref "P34") (pin "1") (pinfunction "1_1") (pintype "passive"))
      (node (ref "P35") (pin "1") (pinfunction "1_1") (pintype "passive"))
      (node (ref "P36") (pin "1") (pinfunction "1_1") (pintype "passive"))
      (node (ref "P37") (pin "1") (pinfunction "1_1") (pintype "passive"))
      (node (ref "P38") (pin "1") (pinfunction "1_1") (pintype "passive"))
      (node (ref "P39") (pin "1") (pinfunction "1_1") (pintype "passive"))
      (node (ref "U25") (pin "10") (pinfunction "VDD_10") (pintype "power_in"))
      (node (ref "U25") (pin "15") (pinfunction "VDD_15") (pintype "power_in"))
      (node (ref "U26") (pin "10") (pinfunction "VDD_10") (pintype "power_in"))
      (node (ref "U26") (pin "15") (pinfunction "VDD_15") (pintype "power_in"))
    )
    (net (code "96") (name "unconnected-(P24-Pad2)") (class "Default")
      (node (ref "P24") (pin "2") (pinfunction "2_2") (pintype "passive+no_connect"))
    )
    (net (code "97") (name "unconnected-(P25-Pad2)") (class "Default")
      (node (ref "P25") (pin "2") (pinfunction "2_2") (pintype "passive+no_connect"))
    )
    (net (code "98") (name "unconnected-(P26-Pad2)") (class "Default")
      (node (ref "P26") (pin "2") (pinfunction "2_2") (pintype "passive+no_connect"))
    )
    (net (code "99") (name "unconnected-(P27-Pad2)") (class "Default")
      (node (ref "P27") (pin "2") (pinfunction "2_2") (pintype "passive+no_connect"))
    )
    (net (code "100") (name "unconnected-(P28-Pad2)") (class "Default")
      (node (ref "P28") (pin "2") (pinfunction "2_2") (pintype "passive+no_connect"))
    )
    (net (code "101") (name "unconnected-(P29-Pad2)") (class "Default")
      (node (ref "P29") (pin "2") (pinfunction "2_2") (pintype "passive+no_connect"))
    )
    (net (code "102") (name "unconnected-(P30-Pad2)") (class "Default")
      (node (ref "P30") (pin "2") (pinfunction "2_2") (pintype "passive+no_connect"))
    )
    (net (code "103") (name "unconnected-(P31-Pad2)") (class "Default")
      (node (ref "P31") (pin "2") (pinfunction "2_2") (pintype "passive+no_connect"))
    )
    (net (code "104") (name "unconnected-(U24-VREF-Pad5)") (class "Default")
      (node (ref "U24") (pin "5") (pinfunction "VREF_5") (pintype "output+no_connect"))
    )
  )
)
